# uhu-adapter.net
KiCad netlist of a schematic drawn in EAGLE
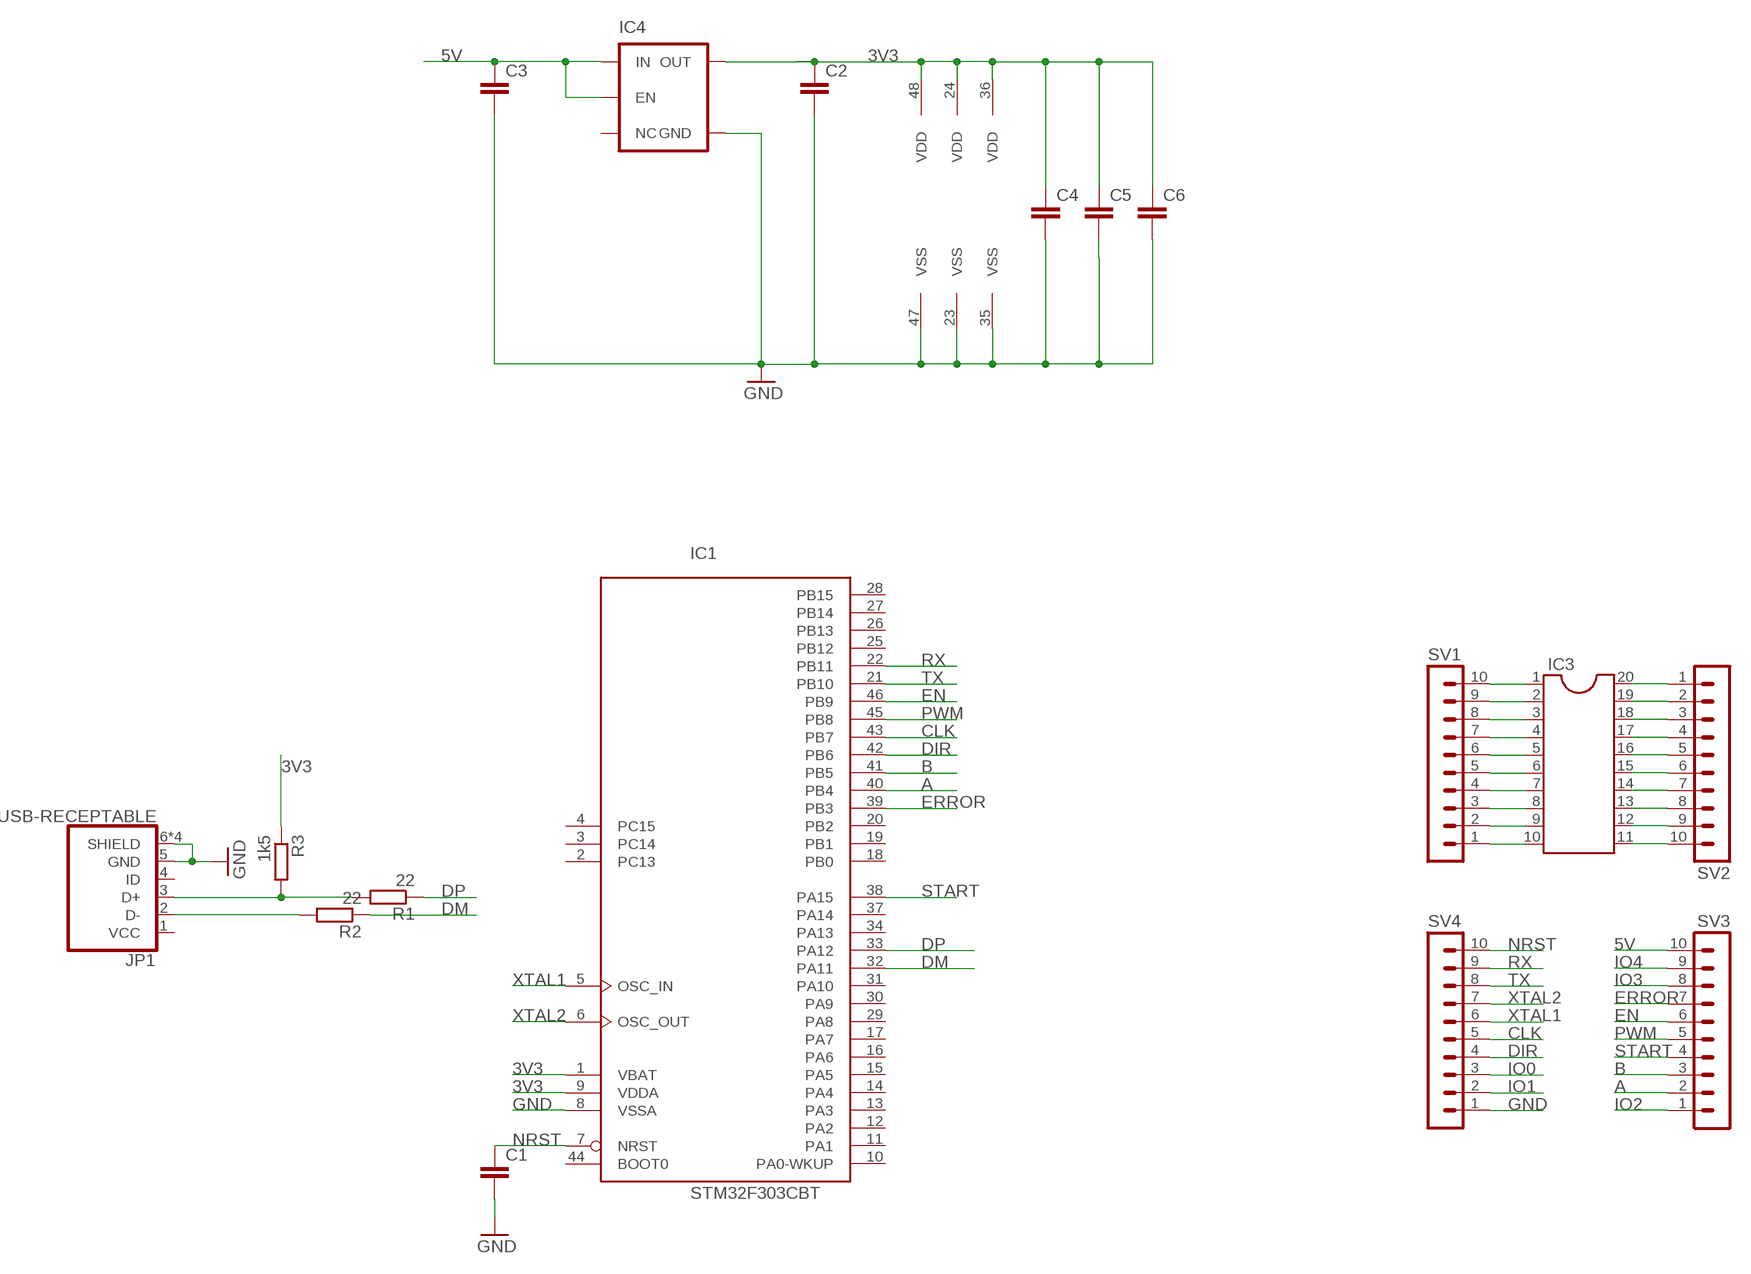
[diagram p0: schematic, sheet 1]

(export (version "E")
  (design (tool "Eeschema 10.0.6"))
  (components
    (comp (ref "C1")
      (value "C-EUC0603")
      (footprint "eagle-import:C0603")
      (libsource (lib "eagle-import") (part "C-EUC0603"))
    )
    (comp (ref "C2")
      (value "C-EUC0603")
      (footprint "eagle-import:C0603")
      (libsource (lib "eagle-import") (part "C-EUC0603"))
    )
    (comp (ref "C3")
      (value "C-EUC0603")
      (footprint "eagle-import:C0603")
      (libsource (lib "eagle-import") (part "C-EUC0603"))
    )
    (comp (ref "C4")
      (value "C-EUC0603")
      (footprint "eagle-import:C0603")
      (libsource (lib "eagle-import") (part "C-EUC0603"))
    )
    (comp (ref "C5")
      (value "C-EUC0603")
      (footprint "eagle-import:C0603")
      (libsource (lib "eagle-import") (part "C-EUC0603"))
    )
    (comp (ref "C6")
      (value "C-EUC0603")
      (footprint "eagle-import:C0603")
      (libsource (lib "eagle-import") (part "C-EUC0603"))
    )
    (comp (ref "IC1")
      (value "STM32F303CBT")
      (footprint "eagle-import:LQFP48")
      (libsource (lib "eagle-import") (part "STM32F303CTB"))
    )
    (comp (ref "IC3")
      (value "DIL20")
      (footprint "eagle-import:DIL20")
      (libsource (lib "eagle-import") (part "DIL20"))
    )
    (comp (ref "IC4")
      (value "V_REG_TPS76433SOT23-5")
      (footprint "eagle-import:SOT23-5")
      (libsource (lib "eagle-import") (part "V_REG_TPS76433SOT23-5"))
    )
    (comp (ref "JP1")
      (value "USB-RECEPTABLE")
      (footprint "eagle-import:FCI-10103594-0001LF")
      (libsource (lib "eagle-import") (part "USB-RECEPTABLE"))
    )
    (comp (ref "R1")
      (value "22")
      (footprint "eagle-import:R0603")
      (libsource (lib "eagle-import") (part "R-EU_R0603"))
    )
    (comp (ref "R2")
      (value "22")
      (footprint "eagle-import:R0603")
      (libsource (lib "eagle-import") (part "R-EU_R0603"))
    )
    (comp (ref "R3")
      (value "1k5")
      (footprint "eagle-import:R0603")
      (libsource (lib "eagle-import") (part "R-EU_R0603"))
    )
    (comp (ref "SV1")
      (value "MA10-1")
      (footprint "eagle-import:MA10-1")
      (libsource (lib "eagle-import") (part "MA10-1"))
    )
    (comp (ref "SV2")
      (value "MA10-1")
      (footprint "eagle-import:MA10-1")
      (libsource (lib "eagle-import") (part "MA10-1"))
    )
    (comp (ref "SV3")
      (value "MA10-1")
      (footprint "eagle-import:MA10-1")
      (libsource (lib "eagle-import") (part "MA10-1"))
    )
    (comp (ref "SV4")
      (value "MA10-1")
      (footprint "eagle-import:MA10-1")
      (libsource (lib "eagle-import") (part "MA10-1"))
    )
  )
  (nets
    (net (code "1") (name "/3V3") (class "Default")
      (node (ref "C2") (pin "1") (pinfunction "1_1") (pintype "passive"))
      (node (ref "C4") (pin "1") (pinfunction "1_1") (pintype "passive"))
      (node (ref "C5") (pin "1") (pinfunction "1_1") (pintype "passive"))
      (node (ref "C6") (pin "1") (pinfunction "1_1") (pintype "passive"))
      (node (ref "IC1") (pin "1") (pinfunction "VBAT_1") (pintype "power_in"))
      (node (ref "IC1") (pin "24") (pinfunction "VDD_24") (pintype "power_in"))
      (node (ref "IC1") (pin "36") (pinfunction "VDD_36") (pintype "power_in"))
      (node (ref "IC1") (pin "48") (pinfunction "VDD_48") (pintype "power_in"))
      (node (ref "IC1") (pin "9") (pinfunction "VDDA_9") (pintype "power_in"))
      (node (ref "IC4") (pin "5") (pinfunction "OUT_5") (pintype "passive"))
      (node (ref "R3") (pin "1") (pinfunction "1_1") (pintype "passive"))
    )
    (net (code "2") (name "/5V") (class "Default")
      (node (ref "C3") (pin "1") (pinfunction "1_1") (pintype "passive"))
      (node (ref "IC4") (pin "1") (pinfunction "IN_1") (pintype "input"))
      (node (ref "IC4") (pin "3") (pinfunction "EN_3") (pintype "input"))
      (node (ref "SV3") (pin "10") (pinfunction "10_10") (pintype "passive"))
    )
    (net (code "3") (name "/A") (class "Default")
      (node (ref "IC1") (pin "40") (pinfunction "PB4_40") (pintype "bidirectional"))
      (node (ref "SV3") (pin "2") (pinfunction "2_2") (pintype "passive"))
    )
    (net (code "4") (name "/B") (class "Default")
      (node (ref "IC1") (pin "41") (pinfunction "PB5_41") (pintype "bidirectional"))
      (node (ref "SV3") (pin "3") (pinfunction "3_3") (pintype "passive"))
    )
    (net (code "5") (name "/CLK") (class "Default")
      (node (ref "IC1") (pin "43") (pinfunction "PB7_43") (pintype "bidirectional"))
      (node (ref "SV4") (pin "5") (pinfunction "5_5") (pintype "passive"))
    )
    (net (code "6") (name "/DIR") (class "Default")
      (node (ref "IC1") (pin "42") (pinfunction "PB6_42") (pintype "bidirectional"))
      (node (ref "SV4") (pin "4") (pinfunction "4_4") (pintype "passive"))
    )
    (net (code "7") (name "/DM") (class "Default")
      (node (ref "IC1") (pin "32") (pinfunction "PA11_32") (pintype "bidirectional"))
      (node (ref "R2") (pin "1") (pinfunction "1_1") (pintype "passive"))
    )
    (net (code "8") (name "/DP") (class "Default")
      (node (ref "IC1") (pin "33") (pinfunction "PA12_33") (pintype "bidirectional"))
      (node (ref "R1") (pin "1") (pinfunction "1_1") (pintype "passive"))
    )
    (net (code "9") (name "/EN") (class "Default")
      (node (ref "IC1") (pin "46") (pinfunction "PB9_46") (pintype "bidirectional"))
      (node (ref "SV3") (pin "6") (pinfunction "6_6") (pintype "passive"))
    )
    (net (code "10") (name "/ERROR") (class "Default")
      (node (ref "IC1") (pin "39") (pinfunction "PB3_39") (pintype "bidirectional"))
      (node (ref "SV3") (pin "7") (pinfunction "7_7") (pintype "passive"))
    )
    (net (code "11") (name "/IO0") (class "Default")
      (node (ref "SV4") (pin "3") (pinfunction "3_3") (pintype "passive"))
    )
    (net (code "12") (name "/IO1") (class "Default")
      (node (ref "SV4") (pin "2") (pinfunction "2_2") (pintype "passive"))
    )
    (net (code "13") (name "/IO2") (class "Default")
      (node (ref "SV3") (pin "1") (pinfunction "1_1") (pintype "passive"))
    )
    (net (code "14") (name "/IO3") (class "Default")
      (node (ref "SV3") (pin "8") (pinfunction "8_8") (pintype "passive"))
    )
    (net (code "15") (name "/IO4") (class "Default")
      (node (ref "SV3") (pin "9") (pinfunction "9_9") (pintype "passive"))
    )
    (net (code "16") (name "/NRST") (class "Default")
      (node (ref "C1") (pin "1") (pinfunction "1_1") (pintype "passive"))
      (node (ref "IC1") (pin "7") (pinfunction "NRST_7") (pintype "bidirectional"))
      (node (ref "SV4") (pin "10") (pinfunction "10_10") (pintype "passive"))
    )
    (net (code "17") (name "/PWM") (class "Default")
      (node (ref "IC1") (pin "45") (pinfunction "PB8_45") (pintype "bidirectional"))
      (node (ref "SV3") (pin "5") (pinfunction "5_5") (pintype "passive"))
    )
    (net (code "18") (name "/RX") (class "Default")
      (node (ref "IC1") (pin "22") (pinfunction "PB11_22") (pintype "bidirectional"))
      (node (ref "SV4") (pin "9") (pinfunction "9_9") (pintype "passive"))
    )
    (net (code "19") (name "/START") (class "Default")
      (node (ref "IC1") (pin "38") (pinfunction "PA15_38") (pintype "bidirectional"))
      (node (ref "SV3") (pin "4") (pinfunction "4_4") (pintype "passive"))
    )
    (net (code "20") (name "/TX") (class "Default")
      (node (ref "IC1") (pin "21") (pinfunction "PB10_21") (pintype "bidirectional"))
      (node (ref "SV4") (pin "8") (pinfunction "8_8") (pintype "passive"))
    )
    (net (code "21") (name "/XTAL1") (class "Default")
      (node (ref "IC1") (pin "5") (pinfunction "OSC_IN_5") (pintype "bidirectional"))
      (node (ref "SV4") (pin "6") (pinfunction "6_6") (pintype "passive"))
    )
    (net (code "22") (name "/XTAL2") (class "Default")
      (node (ref "IC1") (pin "6") (pinfunction "OSC_OUT_6") (pintype "bidirectional"))
      (node (ref "SV4") (pin "7") (pinfunction "7_7") (pintype "passive"))
    )
    (net (code "23") (name "GND") (class "Default")
      (node (ref "C1") (pin "2") (pinfunction "2_2") (pintype "passive"))
      (node (ref "C2") (pin "2") (pinfunction "2_2") (pintype "passive"))
      (node (ref "C3") (pin "2") (pinfunction "2_2") (pintype "passive"))
      (node (ref "C4") (pin "2") (pinfunction "2_2") (pintype "passive"))
      (node (ref "C5") (pin "2") (pinfunction "2_2") (pintype "passive"))
      (node (ref "C6") (pin "2") (pinfunction "2_2") (pintype "passive"))
      (node (ref "IC1") (pin "23") (pinfunction "VSS_23") (pintype "power_in"))
      (node (ref "IC1") (pin "35") (pinfunction "VSS_35") (pintype "power_in"))
      (node (ref "IC1") (pin "47") (pinfunction "VSS_47") (pintype "power_in"))
      (node (ref "IC1") (pin "8") (pinfunction "VSSA_8") (pintype "power_in"))
      (node (ref "IC4") (pin "2") (pinfunction "GND_2") (pintype "input"))
      (node (ref "JP1") (pin "5") (pinfunction "GND_5") (pintype "bidirectional"))
      (node (ref "JP1") (pin "6") (pinfunction "SHIELD_6") (pintype "bidirectional"))
      (node (ref "JP1") (pin "7") (pinfunction "SHIELD_7") (pintype "bidirectional"))
      (node (ref "JP1") (pin "8") (pinfunction "SHIELD_8") (pintype "bidirectional"))
      (node (ref "JP1") (pin "9") (pinfunction "SHIELD_9") (pintype "bidirectional"))
      (node (ref "SV4") (pin "1") (pinfunction "1_1") (pintype "passive"))
    )
    (net (code "24") (name "Net-(IC3-Pad1)") (class "Default")
      (node (ref "IC3") (pin "1") (pinfunction "1_1") (pintype "passive"))
      (node (ref "SV1") (pin "10") (pinfunction "10_10") (pintype "passive"))
    )
    (net (code "25") (name "Net-(IC3-Pad2)") (class "Default")
      (node (ref "IC3") (pin "2") (pinfunction "2_2") (pintype "passive"))
      (node (ref "SV1") (pin "9") (pinfunction "9_9") (pintype "passive"))
    )
    (net (code "26") (name "Net-(IC3-Pad3)") (class "Default")
      (node (ref "IC3") (pin "3") (pinfunction "3_3") (pintype "passive"))
      (node (ref "SV1") (pin "8") (pinfunction "8_8") (pintype "passive"))
    )
    (net (code "27") (name "Net-(IC3-Pad4)") (class "Default")
      (node (ref "IC3") (pin "4") (pinfunction "4_4") (pintype "passive"))
      (node (ref "SV1") (pin "7") (pinfunction "7_7") (pintype "passive"))
    )
    (net (code "28") (name "Net-(IC3-Pad5)") (class "Default")
      (node (ref "IC3") (pin "5") (pinfunction "5_5") (pintype "passive"))
      (node (ref "SV1") (pin "6") (pinfunction "6_6") (pintype "passive"))
    )
    (net (code "29") (name "Net-(IC3-Pad6)") (class "Default")
      (node (ref "IC3") (pin "6") (pinfunction "6_6") (pintype "passive"))
      (node (ref "SV1") (pin "5") (pinfunction "5_5") (pintype "passive"))
    )
    (net (code "30") (name "Net-(IC3-Pad7)") (class "Default")
      (node (ref "IC3") (pin "7") (pinfunction "7_7") (pintype "passive"))
      (node (ref "SV1") (pin "4") (pinfunction "4_4") (pintype "passive"))
    )
    (net (code "31") (name "Net-(IC3-Pad8)") (class "Default")
      (node (ref "IC3") (pin "8") (pinfunction "8_8") (pintype "passive"))
      (node (ref "SV1") (pin "3") (pinfunction "3_3") (pintype "passive"))
    )
    (net (code "32") (name "Net-(IC3-Pad9)") (class "Default")
      (node (ref "IC3") (pin "9") (pinfunction "9_9") (pintype "passive"))
      (node (ref "SV1") (pin "2") (pinfunction "2_2") (pintype "passive"))
    )
    (net (code "33") (name "Net-(IC3-Pad10)") (class "Default")
      (node (ref "IC3") (pin "10") (pinfunction "10_10") (pintype "passive"))
      (node (ref "SV1") (pin "1") (pinfunction "1_1") (pintype "passive"))
    )
    (net (code "34") (name "Net-(IC3-Pad11)") (class "Default")
      (node (ref "IC3") (pin "11") (pinfunction "11_11") (pintype "passive"))
      (node (ref "SV2") (pin "10") (pinfunction "10_10") (pintype "passive"))
    )
    (net (code "35") (name "Net-(IC3-Pad12)") (class "Default")
      (node (ref "IC3") (pin "12") (pinfunction "12_12") (pintype "passive"))
      (node (ref "SV2") (pin "9") (pinfunction "9_9") (pintype "passive"))
    )
    (net (code "36") (name "Net-(IC3-Pad13)") (class "Default")
      (node (ref "IC3") (pin "13") (pinfunction "13_13") (pintype "passive"))
      (node (ref "SV2") (pin "8") (pinfunction "8_8") (pintype "passive"))
    )
    (net (code "37") (name "Net-(IC3-Pad14)") (class "Default")
      (node (ref "IC3") (pin "14") (pinfunction "14_14") (pintype "passive"))
      (node (ref "SV2") (pin "7") (pinfunction "7_7") (pintype "passive"))
    )
    (net (code "38") (name "Net-(IC3-Pad15)") (class "Default")
      (node (ref "IC3") (pin "15") (pinfunction "15_15") (pintype "passive"))
      (node (ref "SV2") (pin "6") (pinfunction "6_6") (pintype "passive"))
    )
    (net (code "39") (name "Net-(IC3-Pad16)") (class "Default")
      (node (ref "IC3") (pin "16") (pinfunction "16_16") (pintype "passive"))
      (node (ref "SV2") (pin "5") (pinfunction "5_5") (pintype "passive"))
    )
    (net (code "40") (name "Net-(IC3-Pad17)") (class "Default")
      (node (ref "IC3") (pin "17") (pinfunction "17_17") (pintype "passive"))
      (node (ref "SV2") (pin "4") (pinfunction "4_4") (pintype "passive"))
    )
    (net (code "41") (name "Net-(IC3-Pad18)") (class "Default")
      (node (ref "IC3") (pin "18") (pinfunction "18_18") (pintype "passive"))
      (node (ref "SV2") (pin "3") (pinfunction "3_3") (pintype "passive"))
    )
    (net (code "42") (name "Net-(IC3-Pad19)") (class "Default")
      (node (ref "IC3") (pin "19") (pinfunction "19_19") (pintype "passive"))
      (node (ref "SV2") (pin "2") (pinfunction "2_2") (pintype "passive"))
    )
    (net (code "43") (name "Net-(IC3-Pad20)") (class "Default")
      (node (ref "IC3") (pin "20") (pinfunction "20_20") (pintype "passive"))
      (node (ref "SV2") (pin "1") (pinfunction "1_1") (pintype "passive"))
    )
    (net (code "44") (name "Net-(JP1-D+)") (class "Default")
      (node (ref "JP1") (pin "3") (pinfunction "D+_3") (pintype "bidirectional"))
      (node (ref "R1") (pin "2") (pinfunction "2_2") (pintype "passive"))
      (node (ref "R3") (pin "2") (pinfunction "2_2") (pintype "passive"))
    )
    (net (code "45") (name "Net-(JP1-D-)") (class "Default")
      (node (ref "JP1") (pin "2") (pinfunction "D-_2") (pintype "bidirectional"))
      (node (ref "R2") (pin "2") (pinfunction "2_2") (pintype "passive"))
    )
    (net (code "46") (name "unconnected-(IC1A-BOOT0-Pad44)") (class "Default")
      (node (ref "IC1") (pin "44") (pinfunction "BOOT0_44") (pintype "input"))
    )
    (net (code "47") (name "unconnected-(IC1A-PA0-WKUP-Pad10)") (class "Default")
      (node (ref "IC1") (pin "10") (pinfunction "PA0-WKUP_10") (pintype "bidirectional"))
    )
    (net (code "48") (name "unconnected-(IC1A-PA1-Pad11)") (class "Default")
      (node (ref "IC1") (pin "11") (pinfunction "PA1_11") (pintype "bidirectional"))
    )
    (net (code "49") (name "unconnected-(IC1A-PA2-Pad12)") (class "Default")
      (node (ref "IC1") (pin "12") (pinfunction "PA2_12") (pintype "bidirectional"))
    )
    (net (code "50") (name "unconnected-(IC1A-PA3-Pad13)") (class "Default")
      (node (ref "IC1") (pin "13") (pinfunction "PA3_13") (pintype "bidirectional"))
    )
    (net (code "51") (name "unconnected-(IC1A-PA4-Pad14)") (class "Default")
      (node (ref "IC1") (pin "14") (pinfunction "PA4_14") (pintype "bidirectional"))
    )
    (net (code "52") (name "unconnected-(IC1A-PA5-Pad15)") (class "Default")
      (node (ref "IC1") (pin "15") (pinfunction "PA5_15") (pintype "bidirectional"))
    )
    (net (code "53") (name "unconnected-(IC1A-PA6-Pad16)") (class "Default")
      (node (ref "IC1") (pin "16") (pinfunction "PA6_16") (pintype "bidirectional"))
    )
    (net (code "54") (name "unconnected-(IC1A-PA7-Pad17)") (class "Default")
      (node (ref "IC1") (pin "17") (pinfunction "PA7_17") (pintype "bidirectional"))
    )
    (net (code "55") (name "unconnected-(IC1A-PA8-Pad29)") (class "Default")
      (node (ref "IC1") (pin "29") (pinfunction "PA8_29") (pintype "bidirectional"))
    )
    (net (code "56") (name "unconnected-(IC1A-PA9-Pad30)") (class "Default")
      (node (ref "IC1") (pin "30") (pinfunction "PA9_30") (pintype "bidirectional"))
    )
    (net (code "57") (name "unconnected-(IC1A-PA10-Pad31)") (class "Default")
      (node (ref "IC1") (pin "31") (pinfunction "PA10_31") (pintype "bidirectional"))
    )
    (net (code "58") (name "unconnected-(IC1A-PA13-Pad34)") (class "Default")
      (node (ref "IC1") (pin "34") (pinfunction "PA13_34") (pintype "bidirectional"))
    )
    (net (code "59") (name "unconnected-(IC1A-PA14-Pad37)") (class "Default")
      (node (ref "IC1") (pin "37") (pinfunction "PA14_37") (pintype "bidirectional"))
    )
    (net (code "60") (name "unconnected-(IC1A-PB0-Pad18)") (class "Default")
      (node (ref "IC1") (pin "18") (pinfunction "PB0_18") (pintype "bidirectional"))
    )
    (net (code "61") (name "unconnected-(IC1A-PB1-Pad19)") (class "Default")
      (node (ref "IC1") (pin "19") (pinfunction "PB1_19") (pintype "bidirectional"))
    )
    (net (code "62") (name "unconnected-(IC1A-PB2-Pad20)") (class "Default")
      (node (ref "IC1") (pin "20") (pinfunction "PB2_20") (pintype "bidirectional"))
    )
    (net (code "63") (name "unconnected-(IC1A-PB12-Pad25)") (class "Default")
      (node (ref "IC1") (pin "25") (pinfunction "PB12_25") (pintype "bidirectional"))
    )
    (net (code "64") (name "unconnected-(IC1A-PB13-Pad26)") (class "Default")
      (node (ref "IC1") (pin "26") (pinfunction "PB13_26") (pintype "bidirectional"))
    )
    (net (code "65") (name "unconnected-(IC1A-PB14-Pad27)") (class "Default")
      (node (ref "IC1") (pin "27") (pinfunction "PB14_27") (pintype "bidirectional"))
    )
    (net (code "66") (name "unconnected-(IC1A-PB15-Pad28)") (class "Default")
      (node (ref "IC1") (pin "28") (pinfunction "PB15_28") (pintype "bidirectional"))
    )
    (net (code "67") (name "unconnected-(IC1A-PC13-Pad2)") (class "Default")
      (node (ref "IC1") (pin "2") (pinfunction "PC13_2") (pintype "bidirectional"))
    )
    (net (code "68") (name "unconnected-(IC1A-PC14-Pad3)") (class "Default")
      (node (ref "IC1") (pin "3") (pinfunction "PC14_3") (pintype "bidirectional"))
    )
    (net (code "69") (name "unconnected-(IC1A-PC15-Pad4)") (class "Default")
      (node (ref "IC1") (pin "4") (pinfunction "PC15_4") (pintype "bidirectional"))
    )
    (net (code "70") (name "unconnected-(IC4-NC-Pad4)") (class "Default")
      (node (ref "IC4") (pin "4") (pinfunction "NC_4") (pintype "input"))
    )
    (net (code "71") (name "unconnected-(JP1-ID-Pad4)") (class "Default")
      (node (ref "JP1") (pin "4") (pinfunction "ID_4") (pintype "bidirectional"))
    )
    (net (code "72") (name "unconnected-(JP1-VCC-Pad1)") (class "Default")
      (node (ref "JP1") (pin "1") (pinfunction "VCC_1") (pintype "bidirectional"))
    )
  )
)
